# CAN_Bus_Network.net
KiCad netlist of a schematic drawn in Altium Designer
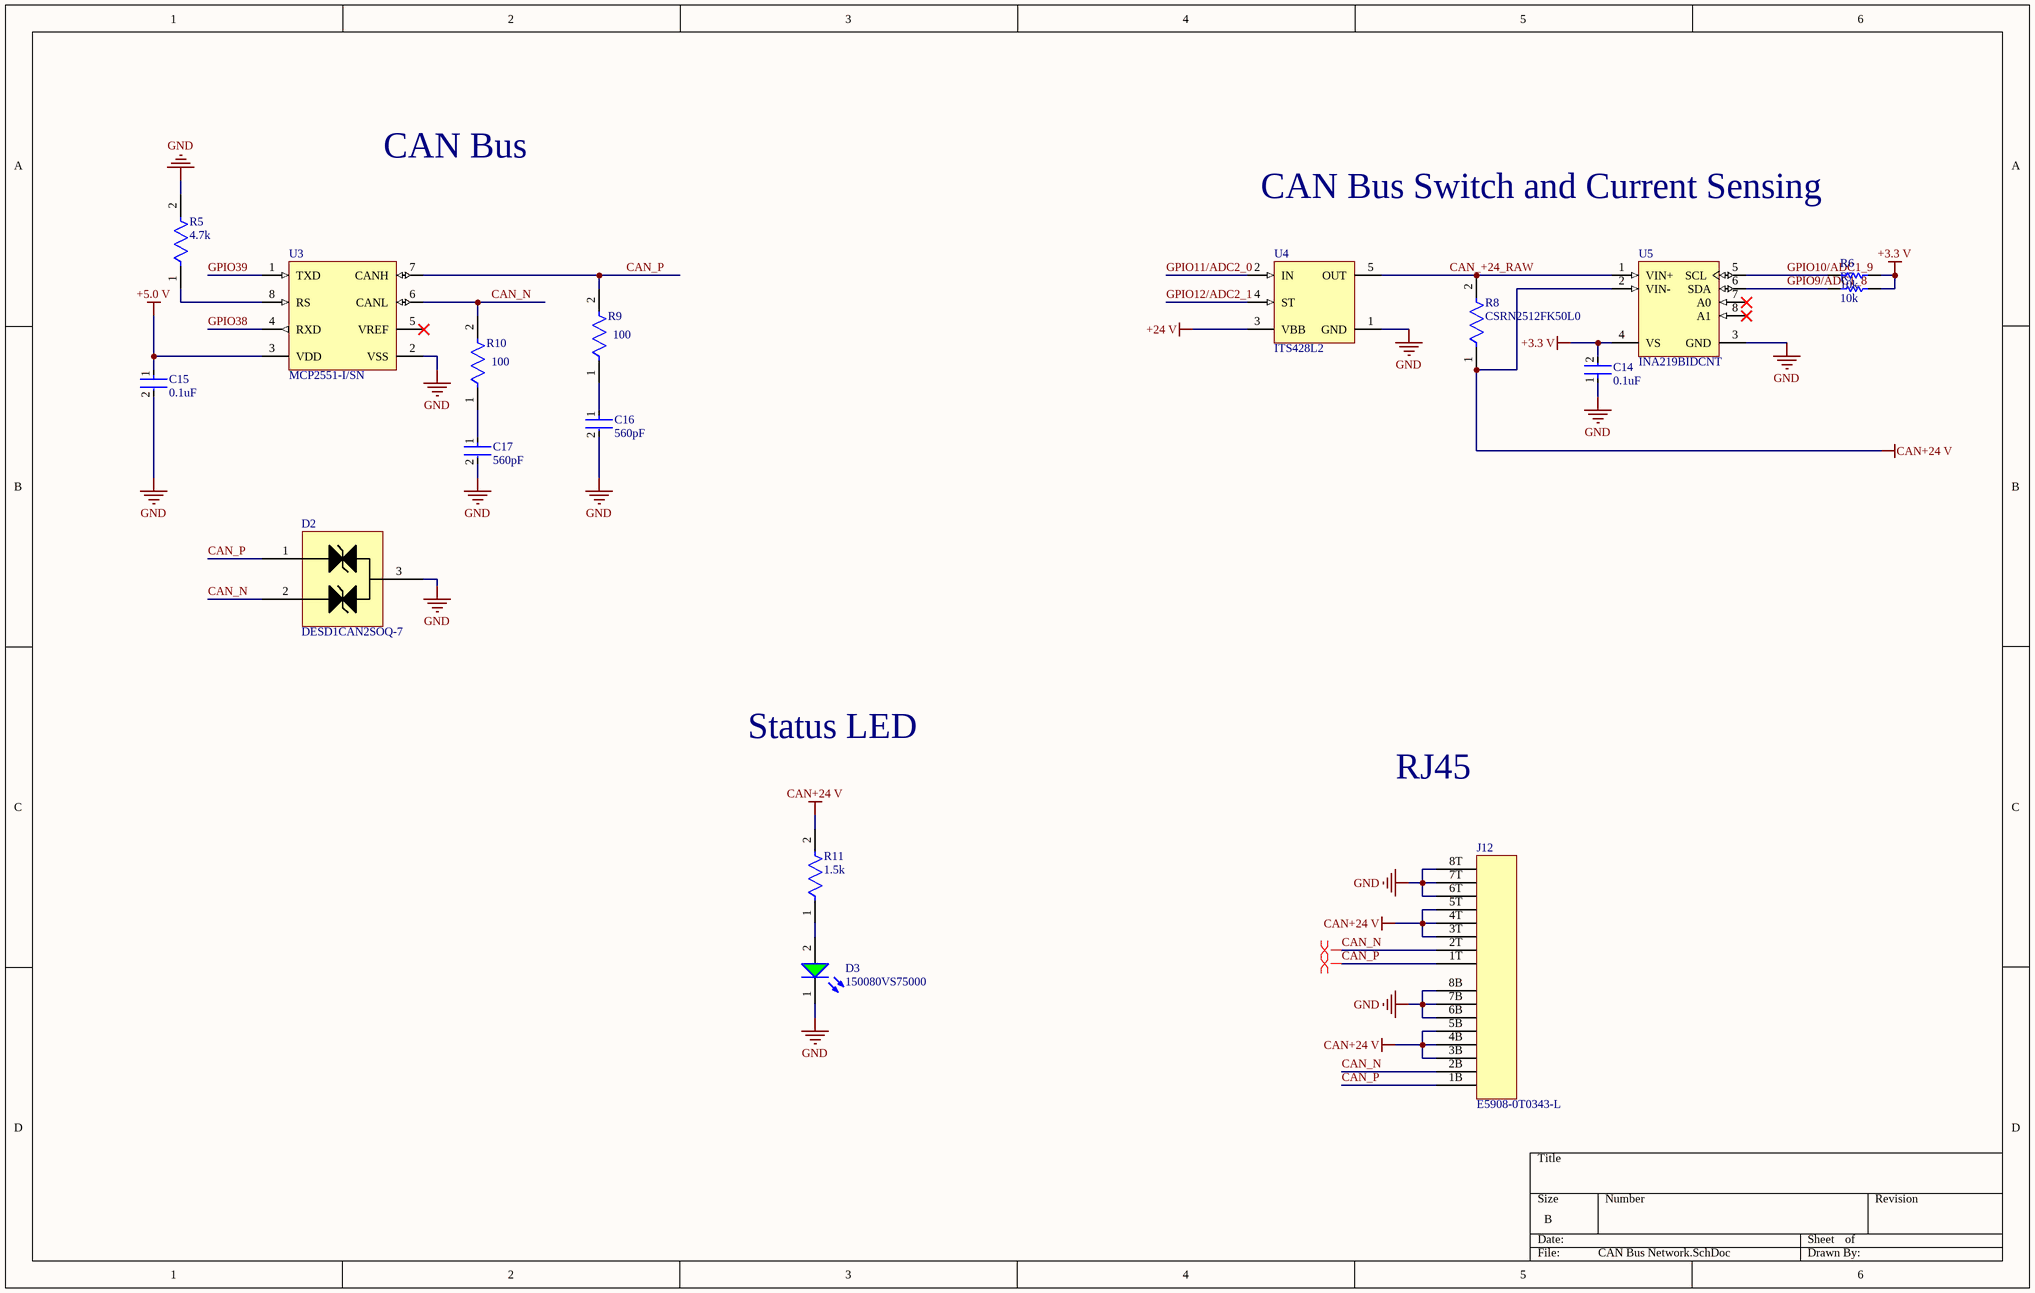
[diagram p0: CAN Bus Network.SchDoc]

(export (version "E")
  (design (tool "Eeschema 10.0.6"))
  (components
    (comp (ref "C14")
      (value "0.1uF")
      (footprint "FP-CC0603-DA-IPC_A")
      (libsource (lib "C0514760 C0514760") (part "11868f565c42a9108669ba33697ecf6"))
    )
    (comp (ref "C15")
      (value "0.1uF")
      (footprint "FP-CC0603-DA-IPC_A")
      (libsource (lib "C0514760 C0514760") (part "11868f565c42a9108669ba33697ecf6"))
    )
    (comp (ref "C16")
      (value "560pF")
      (footprint "FP-CC1206-1_25-IPC_A")
      (libsource (lib "C0514760 C0514760") (part "11868f565c42a9108669ba33697ecf6"))
    )
    (comp (ref "C17")
      (value "560pF")
      (footprint "FP-CC1206-1_25-IPC_A")
      (libsource (lib "C0514760 C0514760") (part "11868f565c42a9108669ba33697ecf6"))
    )
    (comp (ref "D2")
      (value "DESD1CAN2SOQ-7")
      (footprint "SOT95P245X110-3N")
      (description "Trans Voltage Suppressor Diode, 200W, 24V V(RWM), Bidirectional, 2 Element, Silicon")
      (libsource (lib "C0514760 C0514760") (part "DESD1CAN2SOQ-7-Symbol-1"))
    )
    (comp (ref "D3")
      (value "150080VS75000")
      (footprint "WL-SMCW_0805_150080xx75000")
      (description "Single Color LED, Bright Green, Water Clear, 1.4mm")
      (libsource (lib "C0514760 C0514760") (part "LED_Green_2A-1K"))
    )
    (comp (ref "J12")
      (value "E5908-0T0343-L")
      (footprint "E5908-0T0343-L-Footprint-1")
      (description "Telecom and Datacom Connector, 16 Contact(s), Female, Right Angle, Solder Terminal, Jack")
      (libsource (lib "C0514760 C0514760") (part "E5908-0T0343-L-Symbol-1"))
    )
    (comp (ref "R5")
      (value "4.7k")
      (footprint "FP-RT0805-IPC_A")
      (description "Fixed Resistor, Thin Film, 0.125W, 4700ohm, 150V, 1% +/-Tol, 50ppm/Cel, Surface Mount, 0805")
      (fields (field (name "TOLERANCE") "1%") (field (name "POWER") "125mW"))
      (libsource (lib "C0514760 C0514760") (part "1029c3af85768c4190bb7ad29bc67b5"))
    )
    (comp (ref "R6")
      (value "10k")
      (footprint "RESC2013X60X35ML10T20")
      (fields (field (name "TOLERANCE") "1%") (field (name "POWER") "125mW"))
      (libsource (lib "C0514760 C0514760") (part "RES"))
    )
    (comp (ref "R7")
      (value "10k")
      (footprint "RESC2013X60X35ML10T20")
      (fields (field (name "TOLERANCE") "1%") (field (name "POWER") "125mW"))
      (libsource (lib "C0514760 C0514760") (part "RES"))
    )
    (comp (ref "R8")
      (value "CSRN2512FK50L0")
      (footprint "FP-CSRN2512-IPC_B")
      (description "Fixed Resistor, Metal Glaze/thick Film, 2W, 0.05ohm, 1% +/-Tol, 200ppm/Cel, Surface Mount, 2512")
      (fields (field (name "POWER") "2W") (field (name "TOLERANCE") "1%"))
      (libsource (lib "C0514760 C0514760") (part "1029c3af85768c4190bb7ad29bc67b5"))
    )
    (comp (ref "R9")
      (value "100")
      (footprint "FP-RT0805-0_6-IPC_A")
      (description "Fixed Resistor, Thin Film, 0.125W, 100ohm, 150V, 0.1% +/-Tol, 25ppm/Cel, Surface Mount, 0805")
      (fields (field (name "POWER") "125mW") (field (name "TOLERANCE") "0.1%"))
      (libsource (lib "C0514760 C0514760") (part "1029c3af85768c4190bb7ad29bc67b5"))
    )
    (comp (ref "R10")
      (value "100")
      (footprint "FP-RT0805-0_6-IPC_A")
      (description "Fixed Resistor, Thin Film, 0.125W, 100ohm, 150V, 0.1% +/-Tol, 25ppm/Cel, Surface Mount, 0805")
      (fields (field (name "POWER") "125mW") (field (name "TOLERANCE") "0.1%"))
      (libsource (lib "C0514760 C0514760") (part "1029c3af85768c4190bb7ad29bc67b5"))
    )
    (comp (ref "R11")
      (value "1.5k")
      (footprint "FP-RT0805-IPC_A")
      (description "Fixed Resistor, Thin Film, 0.125W, 1500ohm, 150V, 1% +/-Tol, 50ppm/Cel, Surface Mount, 0805")
      (fields (field (name "POWER") "125mW") (field (name "TOLERANCE") "1%"))
      (libsource (lib "C0514760 C0514760") (part "1029c3af85768c4190bb7ad29bc67b5"))
    )
    (comp (ref "U3")
      (value "MCP2551-I/SN")
      (footprint "MCHP-SN8_V")
      (description "CAN Transceiver, 1-Trnsvr, PDSO8")
      (libsource (lib "C0514760 C0514760") (part "MCHP-MCP2551-SN8"))
    )
    (comp (ref "U4")
      (value "ITS428L2")
      (footprint "INF-PG-TO252-5-11_M")
      (description "Buffer/Inverter Based Peripheral Driver, 1 Driver, 1.8A, PSSO4")
      (libsource (lib "C0514760 C0514760") (part "INF-ITS428L2-PG-TO252-5-11-5"))
    )
    (comp (ref "U5")
      (value "INA219BIDCNT")
      (footprint "DCN0008A_M")
      (description "Power Supply Support Circuit, Fixed, 2 Channel, 2V, PDSO8")
      (libsource (lib "C0514760 C0514760") (part "TI-INA219DCN8"))
    )
  )
  (nets
    (net (code "1") (name "+3.3 V") (class "Default")
      (node (ref "C14") (pin "2") (pinfunction "2_2") (pintype "passive"))
      (node (ref "R6") (pin "1") (pinfunction "1_1") (pintype "passive"))
      (node (ref "R7") (pin "1") (pinfunction "1_1") (pintype "passive"))
      (node (ref "U5") (pin "4") (pinfunction "VS_4") (pintype "power_in"))
    )
    (net (code "2") (name "+5.0 V") (class "Default")
      (node (ref "C15") (pin "1") (pinfunction "1_1") (pintype "passive"))
      (node (ref "U3") (pin "3") (pinfunction "VDD_3") (pintype "power_in"))
    )
    (net (code "3") (name "+24 V") (class "Default")
      (node (ref "U4") (pin "3") (pinfunction "VBB_3") (pintype "power_in"))
    )
    (net (code "4") (name "/CAN_+24_RAW") (class "Default")
      (node (ref "R8") (pin "2") (pinfunction "2_2") (pintype "passive"))
      (node (ref "U4") (pin "5") (pinfunction "OUT_5") (pintype "power_in"))
      (node (ref "U5") (pin "1") (pinfunction "VIN+_1") (pintype "input"))
    )
    (net (code "5") (name "/CAN_N") (class "Default")
      (node (ref "D2") (pin "2") (pinfunction "2_2") (pintype "passive"))
      (node (ref "J12") (pin "2B") (pinfunction "2B_2B") (pintype "passive"))
      (node (ref "J12") (pin "2T") (pinfunction "2T_2T") (pintype "passive"))
      (node (ref "R10") (pin "2") (pinfunction "2_2") (pintype "passive"))
      (node (ref "U3") (pin "6") (pinfunction "CANL_6") (pintype "bidirectional"))
    )
    (net (code "6") (name "/CAN_P") (class "Default")
      (node (ref "D2") (pin "1") (pinfunction "1_1") (pintype "passive"))
      (node (ref "J12") (pin "1B") (pinfunction "1B_1B") (pintype "passive"))
      (node (ref "J12") (pin "1T") (pinfunction "1T_1T") (pintype "passive"))
      (node (ref "R9") (pin "2") (pinfunction "2_2") (pintype "passive"))
      (node (ref "U3") (pin "7") (pinfunction "CANH_7") (pintype "bidirectional"))
    )
    (net (code "7") (name "/GPIO9{slash}ADC1_8") (class "Default")
      (node (ref "R7") (pin "2") (pinfunction "2_2") (pintype "passive"))
      (node (ref "U5") (pin "6") (pinfunction "SDA_6") (pintype "bidirectional"))
    )
    (net (code "8") (name "/GPIO10{slash}ADC1_9") (class "Default")
      (node (ref "R6") (pin "2") (pinfunction "2_2") (pintype "passive"))
      (node (ref "U5") (pin "5") (pinfunction "SCL_5") (pintype "bidirectional"))
    )
    (net (code "9") (name "/GPIO11{slash}ADC2_0") (class "Default")
      (node (ref "U4") (pin "2") (pinfunction "IN_2") (pintype "input"))
    )
    (net (code "10") (name "/GPIO12{slash}ADC2_1") (class "Default")
      (node (ref "U4") (pin "4") (pinfunction "ST_4") (pintype "input"))
    )
    (net (code "11") (name "/GPIO38") (class "Default")
      (node (ref "U3") (pin "4") (pinfunction "RXD_4") (pintype "output"))
    )
    (net (code "12") (name "/GPIO39") (class "Default")
      (node (ref "U3") (pin "1") (pinfunction "TXD_1") (pintype "input"))
    )
    (net (code "13") (name "CAN+24 V") (class "Default")
      (node (ref "J12") (pin "3B") (pinfunction "3B_3B") (pintype "passive"))
      (node (ref "J12") (pin "3T") (pinfunction "3T_3T") (pintype "passive"))
      (node (ref "J12") (pin "4B") (pinfunction "4B_4B") (pintype "passive"))
      (node (ref "J12") (pin "4T") (pinfunction "4T_4T") (pintype "passive"))
      (node (ref "J12") (pin "5B") (pinfunction "5B_5B") (pintype "passive"))
      (node (ref "J12") (pin "5T") (pinfunction "5T_5T") (pintype "passive"))
      (node (ref "R11") (pin "2") (pinfunction "2_2") (pintype "passive"))
      (node (ref "R8") (pin "1") (pinfunction "1_1") (pintype "passive"))
      (node (ref "U5") (pin "2") (pinfunction "VIN-_2") (pintype "input"))
    )
    (net (code "14") (name "GND") (class "Default")
      (node (ref "C14") (pin "1") (pinfunction "1_1") (pintype "passive"))
      (node (ref "C15") (pin "2") (pinfunction "2_2") (pintype "passive"))
      (node (ref "C16") (pin "2") (pinfunction "2_2") (pintype "passive"))
      (node (ref "C17") (pin "2") (pinfunction "2_2") (pintype "passive"))
      (node (ref "D2") (pin "3") (pinfunction "3_3") (pintype "passive"))
      (node (ref "D3") (pin "1") (pinfunction "K_1") (pintype "passive"))
      (node (ref "J12") (pin "6B") (pinfunction "6B_6B") (pintype "passive"))
      (node (ref "J12") (pin "6T") (pinfunction "6T_6T") (pintype "passive"))
      (node (ref "J12") (pin "7B") (pinfunction "7B_7B") (pintype "passive"))
      (node (ref "J12") (pin "7T") (pinfunction "7T_7T") (pintype "passive"))
      (node (ref "J12") (pin "8B") (pinfunction "8B_8B") (pintype "passive"))
      (node (ref "J12") (pin "8T") (pinfunction "8T_8T") (pintype "passive"))
      (node (ref "R5") (pin "2") (pinfunction "2_2") (pintype "passive"))
      (node (ref "U3") (pin "2") (pinfunction "VSS_2") (pintype "power_in"))
      (node (ref "U4") (pin "1") (pinfunction "GND_1") (pintype "power_in"))
      (node (ref "U5") (pin "3") (pinfunction "GND_3") (pintype "power_in"))
    )
    (net (code "15") (name "Net-(C16-Pad1)") (class "Default")
      (node (ref "C16") (pin "1") (pinfunction "1_1") (pintype "passive"))
      (node (ref "R9") (pin "1") (pinfunction "1_1") (pintype "passive"))
    )
    (net (code "16") (name "Net-(C17-Pad1)") (class "Default")
      (node (ref "C17") (pin "1") (pinfunction "1_1") (pintype "passive"))
      (node (ref "R10") (pin "1") (pinfunction "1_1") (pintype "passive"))
    )
    (net (code "17") (name "Net-(D3-A)") (class "Default")
      (node (ref "D3") (pin "2") (pinfunction "A_2") (pintype "passive"))
      (node (ref "R11") (pin "1") (pinfunction "1_1") (pintype "passive"))
    )
    (net (code "18") (name "Net-(U3-RS)") (class "Default")
      (node (ref "R5") (pin "1") (pinfunction "1_1") (pintype "passive"))
      (node (ref "U3") (pin "8") (pinfunction "RS_8") (pintype "input"))
    )
    (net (code "19") (name "unconnected-(U3-VREF-Pad5)") (class "Default")
      (node (ref "U3") (pin "5") (pinfunction "VREF_5") (pintype "power_in+no_connect"))
    )
    (net (code "20") (name "unconnected-(U5-A0-Pad7)") (class "Default")
      (node (ref "U5") (pin "7") (pinfunction "A0_7") (pintype "input+no_connect"))
    )
    (net (code "21") (name "unconnected-(U5-A1-Pad8)") (class "Default")
      (node (ref "U5") (pin "8") (pinfunction "A1_8") (pintype "input+no_connect"))
    )
  )
)
